# pic18f4550_dev.net
KiCad netlist of a schematic drawn in EAGLE
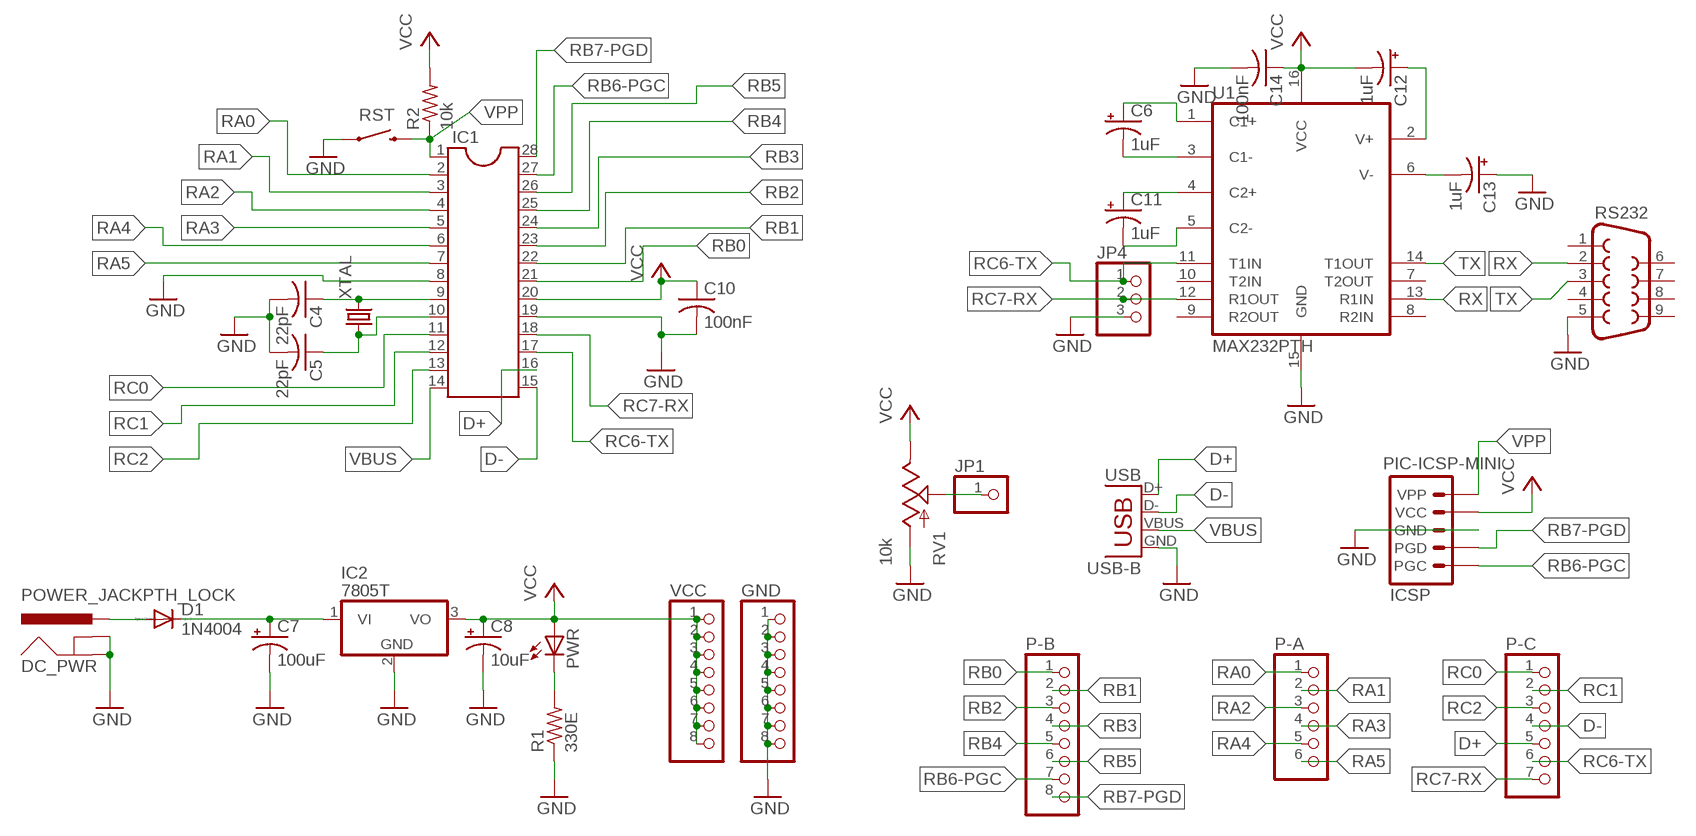
[diagram p0: schematic, sheet 1]

(export (version "E")
  (design (tool "Eeschema 10.0.6"))
  (components
    (comp (ref "C4")
      (value "22pF")
      (footprint "eagle-import:C025-024X044")
      (libsource (lib "eagle-import") (part "C-US025-024X044"))
    )
    (comp (ref "C5")
      (value "22pF")
      (footprint "eagle-import:C025-024X044")
      (libsource (lib "eagle-import") (part "C-US025-024X044"))
    )
    (comp (ref "C6")
      (value "1uF")
      (footprint "eagle-import:CPOL-RADIAL-10UF-25V")
      (libsource (lib "eagle-import") (part "CAP_POLPTH2"))
    )
    (comp (ref "C7")
      (value "100uF")
      (footprint "eagle-import:CPOL-RADIAL-100UF-25V")
      (libsource (lib "eagle-import") (part "CAP_POLPTH1"))
    )
    (comp (ref "C8")
      (value "10uF")
      (footprint "eagle-import:CPOL-RADIAL-10UF-25V")
      (libsource (lib "eagle-import") (part "CAP_POLPTH2"))
    )
    (comp (ref "C10")
      (value "100nF")
      (footprint "eagle-import:C025-025X050")
      (libsource (lib "eagle-import") (part "C-US025-025X050"))
    )
    (comp (ref "C11")
      (value "1uF")
      (footprint "eagle-import:CPOL-RADIAL-10UF-25V")
      (libsource (lib "eagle-import") (part "CAP_POLPTH2"))
    )
    (comp (ref "C12")
      (value "1uF")
      (footprint "eagle-import:CPOL-RADIAL-10UF-25V")
      (libsource (lib "eagle-import") (part "CAP_POLPTH2"))
    )
    (comp (ref "C13")
      (value "1uF")
      (footprint "eagle-import:CPOL-RADIAL-10UF-25V")
      (libsource (lib "eagle-import") (part "CAP_POLPTH2"))
    )
    (comp (ref "C14")
      (value "100nF")
      (footprint "eagle-import:C025-025X050")
      (libsource (lib "eagle-import") (part "C-US025-025X050"))
    )
    (comp (ref "D1")
      (value "1N4004")
      (footprint "eagle-import:DO41-10")
      (libsource (lib "eagle-import") (part "1N4004"))
    )
    (comp (ref "DC_PWR")
      (value "POWER_JACKPTH_LOCK")
      (footprint "eagle-import:POWER_JACK_PTH_LOCK")
      (libsource (lib "eagle-import") (part "POWER_JACKPTH_LOCK"))
    )
    (comp (ref "GND")
      (value "PINHD-1X8")
      (footprint "eagle-import:1X08")
      (libsource (lib "eagle-import") (part "PINHD-1X8"))
    )
    (comp (ref "IC1")
      (value "DIL28-3")
      (footprint "eagle-import:DIL28-3")
      (libsource (lib "eagle-import") (part "DIL28-3"))
    )
    (comp (ref "IC2")
      (value "7805T")
      (footprint "eagle-import:TO220H")
      (libsource (lib "eagle-import") (part "78T05"))
    )
    (comp (ref "ICSP")
      (value "PIC-ICSP-MINI")
      (footprint "eagle-import:PIC-ICSP-MINI")
      (libsource (lib "eagle-import") (part "PIC-ICSP-MINI"))
    )
    (comp (ref "JP1")
      (value "PINHD-1X1")
      (footprint "eagle-import:1X01")
      (libsource (lib "eagle-import") (part "PINHD-1X1"))
    )
    (comp (ref "JP4")
      (value "PINHD-1X3")
      (footprint "eagle-import:1X03")
      (libsource (lib "eagle-import") (part "PINHD-1X3"))
    )
    (comp (ref "P-A")
      (value "PINHD-1X6")
      (footprint "eagle-import:1X06")
      (libsource (lib "eagle-import") (part "PINHD-1X6"))
    )
    (comp (ref "P-B")
      (value "PINHD-1X8")
      (footprint "eagle-import:1X08")
      (libsource (lib "eagle-import") (part "PINHD-1X8"))
    )
    (comp (ref "P-C")
      (value "PINHD-1X7")
      (footprint "eagle-import:1X07")
      (libsource (lib "eagle-import") (part "PINHD-1X7"))
    )
    (comp (ref "PWR")
      (value "LED5MM")
      (footprint "eagle-import:LED5MM")
      (libsource (lib "eagle-import") (part "LED5MM"))
    )
    (comp (ref "R1")
      (value "330E")
      (footprint "eagle-import:0204_7")
      (libsource (lib "eagle-import") (part "R-US_0204/7"))
    )
    (comp (ref "R2")
      (value "10k")
      (footprint "eagle-import:0204_7")
      (libsource (lib "eagle-import") (part "R-US_0204/7"))
    )
    (comp (ref "RS232")
      (value "DB9FEMALE")
      (footprint "eagle-import:DB9")
      (libsource (lib "eagle-import") (part "DB9FEMALE"))
    )
    (comp (ref "RST")
      (value "SWITCH-MOMENTARY-2PTH")
      (footprint "eagle-import:TACTILE-PTH")
      (libsource (lib "eagle-import") (part "SWITCH-MOMENTARY-2PTH"))
    )
    (comp (ref "RV1")
      (value "10k")
      (footprint "eagle-import:TRIM_POT")
      (libsource (lib "eagle-import") (part "POTTRIM"))
    )
    (comp (ref "U1")
      (value "MAX232PTH")
      (footprint "eagle-import:DIL16")
      (libsource (lib "eagle-import") (part "MAX232PTH"))
    )
    (comp (ref "USB")
      (value "USB-B")
      (footprint "eagle-import:USB-B-PTH")
      (libsource (lib "eagle-import") (part "USBPTH"))
    )
    (comp (ref "VCC")
      (value "PINHD-1X8")
      (footprint "eagle-import:1X08")
      (libsource (lib "eagle-import") (part "PINHD-1X8"))
    )
    (comp (ref "XTAL")
      (value "CRYSTALHC49S")
      (footprint "eagle-import:HC49_S")
      (libsource (lib "eagle-import") (part "CRYSTALHC49S"))
    )
  )
  (nets
    (net (code "1") (name "D+") (class "Default")
      (node (ref "IC1") (pin "16") (pinfunction "16_16") (pintype "passive"))
      (node (ref "P-C") (pin "5") (pinfunction "5_5") (pintype "passive"))
      (node (ref "USB") (pin "D+") (pinfunction "D+_D+") (pintype "bidirectional"))
    )
    (net (code "2") (name "D-") (class "Default")
      (node (ref "IC1") (pin "15") (pinfunction "15_15") (pintype "passive"))
      (node (ref "P-C") (pin "4") (pinfunction "4_4") (pintype "passive"))
      (node (ref "USB") (pin "D-") (pinfunction "D-_D-") (pintype "bidirectional"))
    )
    (net (code "3") (name "GND") (class "Default")
      (node (ref "C10") (pin "2") (pinfunction "2_2") (pintype "passive"))
      (node (ref "C13") (pin "1") (pinfunction "+_1") (pintype "passive"))
      (node (ref "C14") (pin "2") (pinfunction "2_2") (pintype "passive"))
      (node (ref "C4") (pin "2") (pinfunction "2_2") (pintype "passive"))
      (node (ref "C5") (pin "2") (pinfunction "2_2") (pintype "passive"))
      (node (ref "C7") (pin "2") (pinfunction "-_2") (pintype "passive"))
      (node (ref "C8") (pin "2") (pinfunction "-_2") (pintype "passive"))
      (node (ref "DC_PWR") (pin "GND") (pinfunction "GND_GND") (pintype "bidirectional"))
      (node (ref "DC_PWR") (pin "GNDBREAK") (pinfunction "GNDBREAK_GNDBREAK") (pintype "bidirectional"))
      (node (ref "GND") (pin "1") (pinfunction "1_1") (pintype "passive"))
      (node (ref "GND") (pin "2") (pinfunction "2_2") (pintype "passive"))
      (node (ref "GND") (pin "3") (pinfunction "3_3") (pintype "passive"))
      (node (ref "GND") (pin "4") (pinfunction "4_4") (pintype "passive"))
      (node (ref "GND") (pin "5") (pinfunction "5_5") (pintype "passive"))
      (node (ref "GND") (pin "6") (pinfunction "6_6") (pintype "passive"))
      (node (ref "GND") (pin "7") (pinfunction "7_7") (pintype "passive"))
      (node (ref "GND") (pin "8") (pinfunction "8_8") (pintype "passive"))
      (node (ref "IC1") (pin "19") (pinfunction "19_19") (pintype "passive"))
      (node (ref "IC1") (pin "8") (pinfunction "8_8") (pintype "passive"))
      (node (ref "IC2") (pin "2") (pinfunction "GND_2") (pintype "passive"))
      (node (ref "ICSP") (pin "3") (pinfunction "GND_3") (pintype "passive"))
      (node (ref "JP4") (pin "3") (pinfunction "3_3") (pintype "passive"))
      (node (ref "R1") (pin "1") (pinfunction "1_1") (pintype "passive"))
      (node (ref "RS232") (pin "5") (pinfunction "5_5") (pintype "passive"))
      (node (ref "RST") (pin "1") (pinfunction "1_1") (pintype "passive"))
      (node (ref "RV1") (pin "3") (pinfunction "A_3") (pintype "passive"))
      (node (ref "U1") (pin "15") (pinfunction "GND_15") (pintype "bidirectional"))
      (node (ref "USB") (pin "GND") (pinfunction "GND_GND") (pintype "bidirectional"))
    )
    (net (code "4") (name "Net-(C4-Pad1)") (class "Default")
      (node (ref "C4") (pin "1") (pinfunction "1_1") (pintype "passive"))
      (node (ref "IC1") (pin "9") (pinfunction "9_9") (pintype "passive"))
      (node (ref "XTAL") (pin "2") (pinfunction "2_2") (pintype "passive"))
    )
    (net (code "5") (name "Net-(C5-Pad1)") (class "Default")
      (node (ref "C5") (pin "1") (pinfunction "1_1") (pintype "passive"))
      (node (ref "IC1") (pin "10") (pinfunction "10_10") (pintype "passive"))
      (node (ref "XTAL") (pin "1") (pinfunction "1_1") (pintype "passive"))
    )
    (net (code "6") (name "Net-(C6-+)") (class "Default")
      (node (ref "C6") (pin "1") (pinfunction "+_1") (pintype "passive"))
      (node (ref "U1") (pin "1") (pinfunction "C1+_1") (pintype "bidirectional"))
    )
    (net (code "7") (name "Net-(C6--)") (class "Default")
      (node (ref "C6") (pin "2") (pinfunction "-_2") (pintype "passive"))
      (node (ref "U1") (pin "3") (pinfunction "C1-_3") (pintype "bidirectional"))
    )
    (net (code "8") (name "Net-(C7-+)") (class "Default")
      (node (ref "C7") (pin "1") (pinfunction "+_1") (pintype "passive"))
      (node (ref "D1") (pin "C") (pinfunction "C_C") (pintype "passive"))
      (node (ref "IC2") (pin "1") (pinfunction "VI_1") (pintype "input"))
    )
    (net (code "9") (name "Net-(C11-+)") (class "Default")
      (node (ref "C11") (pin "1") (pinfunction "+_1") (pintype "passive"))
      (node (ref "U1") (pin "4") (pinfunction "C2+_4") (pintype "bidirectional"))
    )
    (net (code "10") (name "Net-(C11--)") (class "Default")
      (node (ref "C11") (pin "2") (pinfunction "-_2") (pintype "passive"))
      (node (ref "U1") (pin "5") (pinfunction "C2-_5") (pintype "bidirectional"))
    )
    (net (code "11") (name "Net-(C12-+)") (class "Default")
      (node (ref "C12") (pin "1") (pinfunction "+_1") (pintype "passive"))
      (node (ref "U1") (pin "2") (pinfunction "V+_2") (pintype "bidirectional"))
    )
    (net (code "12") (name "Net-(C13--)") (class "Default")
      (node (ref "C13") (pin "2") (pinfunction "-_2") (pintype "passive"))
      (node (ref "U1") (pin "6") (pinfunction "V-_6") (pintype "bidirectional"))
    )
    (net (code "13") (name "Net-(D1-PadA)") (class "Default")
      (node (ref "D1") (pin "A") (pinfunction "A_A") (pintype "passive"))
      (node (ref "DC_PWR") (pin "PWR") (pinfunction "PWR_PWR") (pintype "bidirectional"))
    )
    (net (code "14") (name "Net-(PWR-C)") (class "Default")
      (node (ref "PWR") (pin "K") (pinfunction "C_K") (pintype "passive"))
      (node (ref "R1") (pin "2") (pinfunction "2_2") (pintype "passive"))
    )
    (net (code "15") (name "Net-(RV1-S)") (class "Default")
      (node (ref "JP1") (pin "1") (pinfunction "1_1") (pintype "passive"))
      (node (ref "RV1") (pin "1") (pinfunction "S_1") (pintype "passive"))
    )
    (net (code "16") (name "RA0") (class "Default")
      (node (ref "IC1") (pin "2") (pinfunction "2_2") (pintype "passive"))
      (node (ref "P-A") (pin "1") (pinfunction "1_1") (pintype "passive"))
    )
    (net (code "17") (name "RA1") (class "Default")
      (node (ref "IC1") (pin "3") (pinfunction "3_3") (pintype "passive"))
      (node (ref "P-A") (pin "2") (pinfunction "2_2") (pintype "passive"))
    )
    (net (code "18") (name "RA2") (class "Default")
      (node (ref "IC1") (pin "4") (pinfunction "4_4") (pintype "passive"))
      (node (ref "P-A") (pin "3") (pinfunction "3_3") (pintype "passive"))
    )
    (net (code "19") (name "RA3") (class "Default")
      (node (ref "IC1") (pin "5") (pinfunction "5_5") (pintype "passive"))
      (node (ref "P-A") (pin "4") (pinfunction "4_4") (pintype "passive"))
    )
    (net (code "20") (name "RA4") (class "Default")
      (node (ref "IC1") (pin "6") (pinfunction "6_6") (pintype "passive"))
      (node (ref "P-A") (pin "5") (pinfunction "5_5") (pintype "passive"))
    )
    (net (code "21") (name "RA5") (class "Default")
      (node (ref "IC1") (pin "7") (pinfunction "7_7") (pintype "passive"))
      (node (ref "P-A") (pin "6") (pinfunction "6_6") (pintype "passive"))
    )
    (net (code "22") (name "RB0") (class "Default")
      (node (ref "IC1") (pin "21") (pinfunction "21_21") (pintype "passive"))
      (node (ref "P-B") (pin "1") (pinfunction "1_1") (pintype "passive"))
    )
    (net (code "23") (name "RB1") (class "Default")
      (node (ref "IC1") (pin "22") (pinfunction "22_22") (pintype "passive"))
      (node (ref "P-B") (pin "2") (pinfunction "2_2") (pintype "passive"))
    )
    (net (code "24") (name "RB2") (class "Default")
      (node (ref "IC1") (pin "23") (pinfunction "23_23") (pintype "passive"))
      (node (ref "P-B") (pin "3") (pinfunction "3_3") (pintype "passive"))
    )
    (net (code "25") (name "RB3") (class "Default")
      (node (ref "IC1") (pin "24") (pinfunction "24_24") (pintype "passive"))
      (node (ref "P-B") (pin "4") (pinfunction "4_4") (pintype "passive"))
    )
    (net (code "26") (name "RB4") (class "Default")
      (node (ref "IC1") (pin "25") (pinfunction "25_25") (pintype "passive"))
      (node (ref "P-B") (pin "5") (pinfunction "5_5") (pintype "passive"))
    )
    (net (code "27") (name "RB5") (class "Default")
      (node (ref "IC1") (pin "26") (pinfunction "26_26") (pintype "passive"))
      (node (ref "P-B") (pin "6") (pinfunction "6_6") (pintype "passive"))
    )
    (net (code "28") (name "RB6-PGC") (class "Default")
      (node (ref "IC1") (pin "27") (pinfunction "27_27") (pintype "passive"))
      (node (ref "ICSP") (pin "5") (pinfunction "PGC_5") (pintype "passive"))
      (node (ref "P-B") (pin "7") (pinfunction "7_7") (pintype "passive"))
    )
    (net (code "29") (name "RB7-PGD") (class "Default")
      (node (ref "IC1") (pin "28") (pinfunction "28_28") (pintype "passive"))
      (node (ref "ICSP") (pin "4") (pinfunction "PGD_4") (pintype "passive"))
      (node (ref "P-B") (pin "8") (pinfunction "8_8") (pintype "passive"))
    )
    (net (code "30") (name "RC0") (class "Default")
      (node (ref "IC1") (pin "11") (pinfunction "11_11") (pintype "passive"))
      (node (ref "P-C") (pin "1") (pinfunction "1_1") (pintype "passive"))
    )
    (net (code "31") (name "RC1") (class "Default")
      (node (ref "IC1") (pin "12") (pinfunction "12_12") (pintype "passive"))
      (node (ref "P-C") (pin "2") (pinfunction "2_2") (pintype "passive"))
    )
    (net (code "32") (name "RC2") (class "Default")
      (node (ref "IC1") (pin "13") (pinfunction "13_13") (pintype "passive"))
      (node (ref "P-C") (pin "3") (pinfunction "3_3") (pintype "passive"))
    )
    (net (code "33") (name "RC6-TX") (class "Default")
      (node (ref "IC1") (pin "17") (pinfunction "17_17") (pintype "passive"))
      (node (ref "JP4") (pin "1") (pinfunction "1_1") (pintype "passive"))
      (node (ref "P-C") (pin "6") (pinfunction "6_6") (pintype "passive"))
      (node (ref "U1") (pin "11") (pinfunction "T1IN_11") (pintype "input"))
    )
    (net (code "34") (name "RC7-RX") (class "Default")
      (node (ref "IC1") (pin "18") (pinfunction "18_18") (pintype "passive"))
      (node (ref "JP4") (pin "2") (pinfunction "2_2") (pintype "passive"))
      (node (ref "P-C") (pin "7") (pinfunction "7_7") (pintype "passive"))
      (node (ref "U1") (pin "12") (pinfunction "R1OUT_12") (pintype "output"))
    )
    (net (code "35") (name "RX") (class "Default")
      (node (ref "RS232") (pin "2") (pinfunction "2_2") (pintype "passive"))
      (node (ref "U1") (pin "13") (pinfunction "R1IN_13") (pintype "input"))
    )
    (net (code "36") (name "TX") (class "Default")
      (node (ref "RS232") (pin "3") (pinfunction "3_3") (pintype "passive"))
      (node (ref "U1") (pin "14") (pinfunction "T1OUT_14") (pintype "output"))
    )
    (net (code "37") (name "VBUS") (class "Default")
      (node (ref "IC1") (pin "14") (pinfunction "14_14") (pintype "passive"))
      (node (ref "USB") (pin "VBUS") (pinfunction "VBUS_VBUS") (pintype "bidirectional"))
    )
    (net (code "38") (name "VCC") (class "Default")
      (node (ref "C10") (pin "1") (pinfunction "1_1") (pintype "passive"))
      (node (ref "C12") (pin "2") (pinfunction "-_2") (pintype "passive"))
      (node (ref "C14") (pin "1") (pinfunction "1_1") (pintype "passive"))
      (node (ref "C8") (pin "1") (pinfunction "+_1") (pintype "passive"))
      (node (ref "IC1") (pin "20") (pinfunction "20_20") (pintype "passive"))
      (node (ref "IC2") (pin "3") (pinfunction "VO_3") (pintype "passive"))
      (node (ref "ICSP") (pin "2") (pinfunction "VCC_2") (pintype "passive"))
      (node (ref "PWR") (pin "A") (pinfunction "A_A") (pintype "passive"))
      (node (ref "R2") (pin "2") (pinfunction "2_2") (pintype "passive"))
      (node (ref "RV1") (pin "2") (pinfunction "E_2") (pintype "passive"))
      (node (ref "U1") (pin "16") (pinfunction "VCC_16") (pintype "bidirectional"))
      (node (ref "VCC") (pin "1") (pinfunction "1_1") (pintype "passive"))
      (node (ref "VCC") (pin "2") (pinfunction "2_2") (pintype "passive"))
      (node (ref "VCC") (pin "3") (pinfunction "3_3") (pintype "passive"))
      (node (ref "VCC") (pin "4") (pinfunction "4_4") (pintype "passive"))
      (node (ref "VCC") (pin "5") (pinfunction "5_5") (pintype "passive"))
      (node (ref "VCC") (pin "6") (pinfunction "6_6") (pintype "passive"))
      (node (ref "VCC") (pin "7") (pinfunction "7_7") (pintype "passive"))
      (node (ref "VCC") (pin "8") (pinfunction "8_8") (pintype "passive"))
    )
    (net (code "39") (name "VPP") (class "Default")
      (node (ref "IC1") (pin "1") (pinfunction "1_1") (pintype "passive"))
      (node (ref "ICSP") (pin "1") (pinfunction "VPP_1") (pintype "passive"))
      (node (ref "R2") (pin "1") (pinfunction "1_1") (pintype "passive"))
      (node (ref "RST") (pin "3") (pinfunction "2_3") (pintype "passive"))
    )
    (net (code "40") (name "unconnected-(RS232-Pad1)") (class "Default")
      (node (ref "RS232") (pin "1") (pinfunction "1_1") (pintype "passive"))
    )
    (net (code "41") (name "unconnected-(RS232-Pad4)") (class "Default")
      (node (ref "RS232") (pin "4") (pinfunction "4_4") (pintype "passive"))
    )
    (net (code "42") (name "unconnected-(RS232-Pad6)") (class "Default")
      (node (ref "RS232") (pin "6") (pinfunction "6_6") (pintype "passive"))
    )
    (net (code "43") (name "unconnected-(RS232-Pad7)") (class "Default")
      (node (ref "RS232") (pin "7") (pinfunction "7_7") (pintype "passive"))
    )
    (net (code "44") (name "unconnected-(RS232-Pad8)") (class "Default")
      (node (ref "RS232") (pin "8") (pinfunction "8_8") (pintype "passive"))
    )
    (net (code "45") (name "unconnected-(RS232-Pad9)") (class "Default")
      (node (ref "RS232") (pin "9") (pinfunction "9_9") (pintype "passive"))
    )
    (net (code "46") (name "unconnected-(U1-R2IN-Pad8)") (class "Default")
      (node (ref "U1") (pin "8") (pinfunction "R2IN_8") (pintype "input"))
    )
    (net (code "47") (name "unconnected-(U1-R2OUT-Pad9)") (class "Default")
      (node (ref "U1") (pin "9") (pinfunction "R2OUT_9") (pintype "output"))
    )
    (net (code "48") (name "unconnected-(U1-T2IN-Pad10)") (class "Default")
      (node (ref "U1") (pin "10") (pinfunction "T2IN_10") (pintype "input"))
    )
    (net (code "49") (name "unconnected-(U1-T2OUT-Pad7)") (class "Default")
      (node (ref "U1") (pin "7") (pinfunction "T2OUT_7") (pintype "output"))
    )
  )
)
